# scHnRk_4.net
KiCad netlist of a schematic drawn in EAGLE
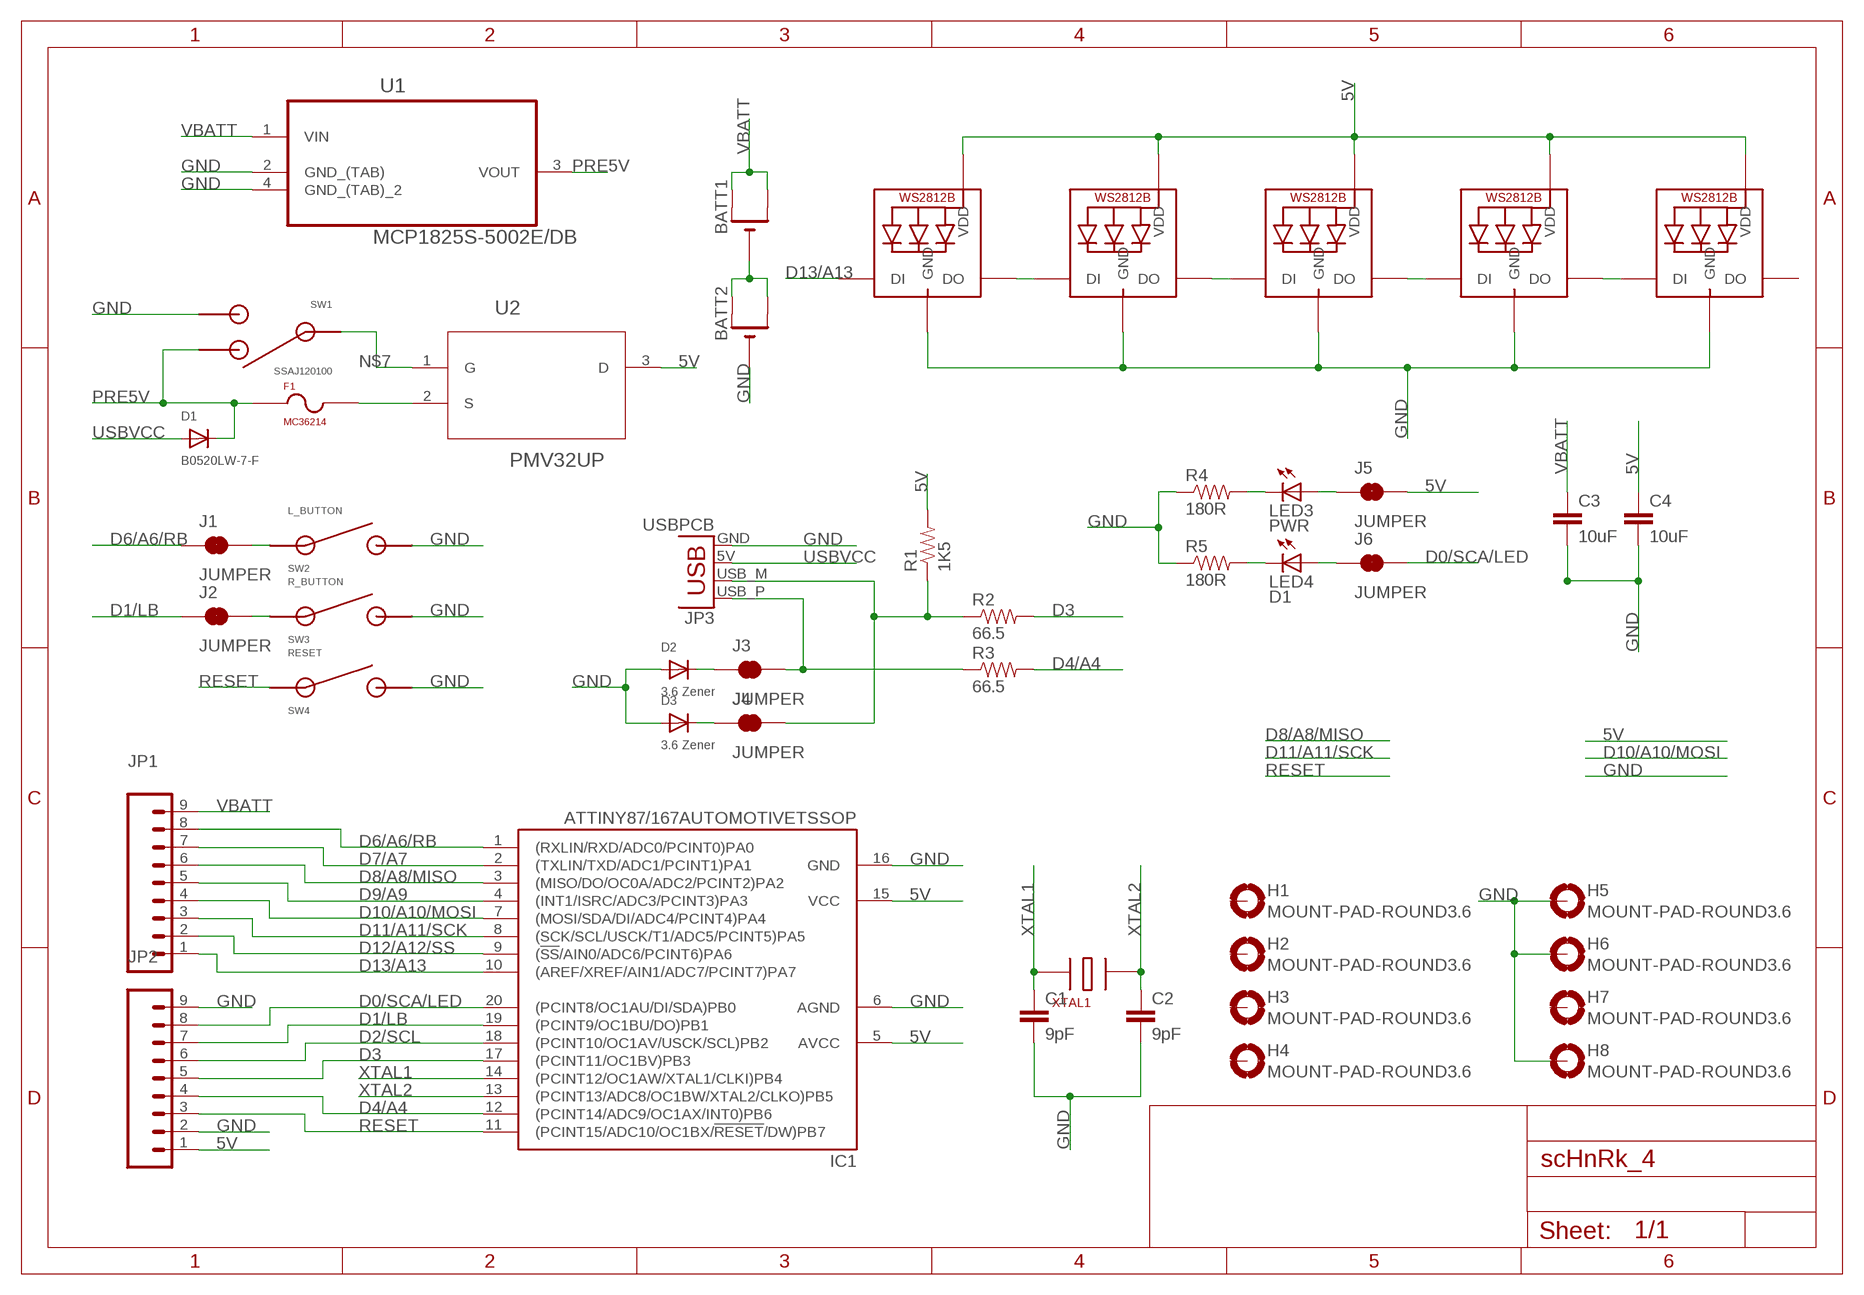
[diagram p0: schematic, sheet 1]

(export (version "E")
  (design (tool "Eeschema 10.0.6"))
  (components
    (comp (ref "BATT1")
      (value "CR2032SMT")
      (footprint "eagle-import:CR2032-SMD")
      (libsource (lib "eagle-import") (part "CR2032SMT"))
    )
    (comp (ref "BATT2")
      (value "CR2032SMT")
      (footprint "eagle-import:CR2032-SMD")
      (libsource (lib "eagle-import") (part "CR2032SMT"))
    )
    (comp (ref "C1")
      (value "9pF")
      (footprint "eagle-import:0603-CAP")
      (libsource (lib "eagle-import") (part "CAP0603-CAP"))
    )
    (comp (ref "C2")
      (value "9pF")
      (footprint "eagle-import:0603-CAP")
      (libsource (lib "eagle-import") (part "CAP0603-CAP"))
    )
    (comp (ref "C3")
      (value "10uF")
      (footprint "eagle-import:0805")
      (libsource (lib "eagle-import") (part "CAP0805"))
    )
    (comp (ref "C4")
      (value "10uF")
      (footprint "eagle-import:0805")
      (libsource (lib "eagle-import") (part "CAP0805"))
    )
    (comp (ref "D1")
      (value "B0520LW-7-F")
      (footprint "eagle-import:SOD-123")
      (libsource (lib "eagle-import") (part "DIODESOD-123"))
    )
    (comp (ref "D2")
      (value "3.6 Zener")
      (footprint "eagle-import:SOD-523")
      (libsource (lib "eagle-import") (part "DIODESOD-523"))
    )
    (comp (ref "D3")
      (value "3.6 Zener")
      (footprint "eagle-import:SOD-523")
      (libsource (lib "eagle-import") (part "DIODESOD-523"))
    )
    (comp (ref "F1")
      (value "MC36214")
      (footprint "eagle-import:MC36214")
      (libsource (lib "eagle-import") (part "MC36214"))
    )
    (comp (ref "H1")
      (value "MOUNT-PAD-ROUND3.6")
      (footprint "eagle-import:3,6-PAD")
      (libsource (lib "eagle-import") (part "MOUNT-PAD-ROUND3.6"))
    )
    (comp (ref "H2")
      (value "MOUNT-PAD-ROUND3.6")
      (footprint "eagle-import:3,6-PAD")
      (libsource (lib "eagle-import") (part "MOUNT-PAD-ROUND3.6"))
    )
    (comp (ref "H3")
      (value "MOUNT-PAD-ROUND3.6")
      (footprint "eagle-import:3,6-PAD")
      (libsource (lib "eagle-import") (part "MOUNT-PAD-ROUND3.6"))
    )
    (comp (ref "H4")
      (value "MOUNT-PAD-ROUND3.6")
      (footprint "eagle-import:3,6-PAD")
      (libsource (lib "eagle-import") (part "MOUNT-PAD-ROUND3.6"))
    )
    (comp (ref "H5")
      (value "MOUNT-PAD-ROUND3.6")
      (footprint "eagle-import:3,6-PAD")
      (libsource (lib "eagle-import") (part "MOUNT-PAD-ROUND3.6"))
    )
    (comp (ref "H6")
      (value "MOUNT-PAD-ROUND3.6")
      (footprint "eagle-import:3,6-PAD")
      (libsource (lib "eagle-import") (part "MOUNT-PAD-ROUND3.6"))
    )
    (comp (ref "H7")
      (value "MOUNT-PAD-ROUND3.6")
      (footprint "eagle-import:3,6-PAD")
      (libsource (lib "eagle-import") (part "MOUNT-PAD-ROUND3.6"))
    )
    (comp (ref "H8")
      (value "MOUNT-PAD-ROUND3.6")
      (footprint "eagle-import:3,6-PAD")
      (libsource (lib "eagle-import") (part "MOUNT-PAD-ROUND3.6"))
    )
    (comp (ref "IC1")
      (value "ATTINY87/167AUTOMOTIVETSSOP")
      (footprint "eagle-import:TSSOP20")
      (libsource (lib "eagle-import") (part "ATTINY87/167AUTOMOTIVETSSOP"))
    )
    (comp (ref "J1")
      (value "JUMPER")
      (footprint "eagle-import:PAD-JUMPER-2-NC_BY_TRACE_YES_SILK")
      (libsource (lib "eagle-import") (part "JUMPER-PAD-2-NC_BY_TRACE"))
    )
    (comp (ref "J2")
      (value "JUMPER")
      (footprint "eagle-import:PAD-JUMPER-2-NC_BY_TRACE_YES_SILK")
      (libsource (lib "eagle-import") (part "JUMPER-PAD-2-NC_BY_TRACE"))
    )
    (comp (ref "J3")
      (value "JUMPER")
      (footprint "eagle-import:PAD-JUMPER-2-NC_BY_TRACE_YES_SILK")
      (libsource (lib "eagle-import") (part "JUMPER-PAD-2-NC_BY_TRACE"))
    )
    (comp (ref "J4")
      (value "JUMPER")
      (footprint "eagle-import:PAD-JUMPER-2-NC_BY_TRACE_YES_SILK")
      (libsource (lib "eagle-import") (part "JUMPER-PAD-2-NC_BY_TRACE"))
    )
    (comp (ref "J5")
      (value "JUMPER")
      (footprint "eagle-import:PAD-JUMPER-2-NC_BY_TRACE_YES_SILK")
      (libsource (lib "eagle-import") (part "JUMPER-PAD-2-NC_BY_TRACE"))
    )
    (comp (ref "J6")
      (value "JUMPER")
      (footprint "eagle-import:PAD-JUMPER-2-NC_BY_TRACE_YES_SILK")
      (libsource (lib "eagle-import") (part "JUMPER-PAD-2-NC_BY_TRACE"))
    )
    (comp (ref "JP1")
      (value "M09")
      (footprint "eagle-import:1X09")
      (libsource (lib "eagle-import") (part "M09"))
    )
    (comp (ref "JP2")
      (value "M09")
      (footprint "eagle-import:1X09")
      (libsource (lib "eagle-import") (part "M09"))
    )
    (comp (ref "JP3")
      (value "USBPCB")
      (footprint "eagle-import:USB-A-PCB")
      (libsource (lib "eagle-import") (part "USBPCB"))
    )
    (comp (ref "LED1")
      (value "WS2812B5050")
      (footprint "eagle-import:WS2812B")
      (libsource (lib "eagle-import") (part "WS2812B5050"))
    )
    (comp (ref "LED2")
      (value "WS2812B5050")
      (footprint "eagle-import:WS2812B")
      (libsource (lib "eagle-import") (part "WS2812B5050"))
    )
    (comp (ref "LED3")
      (value "PWR")
      (footprint "eagle-import:CHIPLED_0603")
      (libsource (lib "eagle-import") (part "LEDCHIPLED_0603"))
    )
    (comp (ref "LED4")
      (value "D1")
      (footprint "eagle-import:CHIPLED_0603")
      (libsource (lib "eagle-import") (part "LEDCHIPLED_0603"))
    )
    (comp (ref "LED5")
      (value "WS2812B5050")
      (footprint "eagle-import:WS2812B")
      (libsource (lib "eagle-import") (part "WS2812B5050"))
    )
    (comp (ref "LED6")
      (value "WS2812B5050")
      (footprint "eagle-import:WS2812B")
      (libsource (lib "eagle-import") (part "WS2812B5050"))
    )
    (comp (ref "LED7")
      (value "WS2812B5050")
      (footprint "eagle-import:WS2812B")
      (libsource (lib "eagle-import") (part "WS2812B5050"))
    )
    (comp (ref "R1")
      (value "1K5")
      (footprint "eagle-import:0805")
      (libsource (lib "eagle-import") (part "RESISTOR0805-RES"))
    )
    (comp (ref "R2")
      (value "66.5")
      (footprint "eagle-import:0603-RES")
      (libsource (lib "eagle-import") (part "RESISTOR0603-RES"))
    )
    (comp (ref "R3")
      (value "66.5")
      (footprint "eagle-import:0603-RES")
      (libsource (lib "eagle-import") (part "RESISTOR0603-RES"))
    )
    (comp (ref "R4")
      (value "180R")
      (footprint "eagle-import:0805")
      (libsource (lib "eagle-import") (part "RESISTOR0805-RES"))
    )
    (comp (ref "R5")
      (value "180R")
      (footprint "eagle-import:0805")
      (libsource (lib "eagle-import") (part "RESISTOR0805-RES"))
    )
    (comp (ref "SW1")
      (value "SSAJ120100")
      (footprint "eagle-import:SSAJ120100")
      (libsource (lib "eagle-import") (part "SSAJ120100"))
    )
    (comp (ref "SW2")
      (value "L_BUTTON")
      (footprint "eagle-import:SKRBAGE010")
      (libsource (lib "eagle-import") (part "SKRBAGE010"))
    )
    (comp (ref "SW3")
      (value "R_BUTTON")
      (footprint "eagle-import:SKRBAGE010")
      (libsource (lib "eagle-import") (part "SKRBAGE010"))
    )
    (comp (ref "SW4")
      (value "RESET")
      (footprint "eagle-import:SKRBAGE010")
      (libsource (lib "eagle-import") (part "SKRBAGE010"))
    )
    (comp (ref "U1")
      (value "MCP1825S-5002E/DB")
      (footprint "eagle-import:SOT230P700X180-4N")
      (libsource (lib "eagle-import") (part "MCP1825S-5002E/DB"))
    )
    (comp (ref "U2")
      (value "PMV32UP")
      (footprint "eagle-import:SOT95P230X110-3N")
      (libsource (lib "eagle-import") (part "PMV32UP"))
    )
    (comp (ref "XTAL1")
      (value "16MHZ-2467444")
      (footprint "eagle-import:16MHZ-2467444")
      (libsource (lib "eagle-import") (part "16MHZ-2467444"))
    )
  )
  (nets
    (net (code "1") (name "/5V") (class "Default")
      (node (ref "C4") (pin "1") (pinfunction "1_1") (pintype "passive"))
      (node (ref "IC1") (pin "15") (pinfunction "VCC_15") (pintype "power_in"))
      (node (ref "IC1") (pin "5") (pinfunction "AVCC_5") (pintype "bidirectional"))
      (node (ref "J5") (pin "2") (pinfunction "2_2") (pintype "passive"))
      (node (ref "JP2") (pin "1") (pinfunction "1_1") (pintype "passive"))
      (node (ref "LED1") (pin "1-VDD") (pinfunction "VDD_1-VDD") (pintype "power_in"))
      (node (ref "LED2") (pin "1-VDD") (pinfunction "VDD_1-VDD") (pintype "power_in"))
      (node (ref "LED5") (pin "1-VDD") (pinfunction "VDD_1-VDD") (pintype "power_in"))
      (node (ref "LED6") (pin "1-VDD") (pinfunction "VDD_1-VDD") (pintype "power_in"))
      (node (ref "LED7") (pin "1-VDD") (pinfunction "VDD_1-VDD") (pintype "power_in"))
      (node (ref "R1") (pin "2") (pinfunction "2_2") (pintype "passive"))
      (node (ref "U2") (pin "3") (pinfunction "D_3") (pintype "passive"))
    )
    (net (code "2") (name "/D0{slash}SCA{slash}LED") (class "Default")
      (node (ref "IC1") (pin "20") (pinfunction "(PCINT8/OC1AU/DI/SDA)PB0_20") (pintype "bidirectional"))
      (node (ref "J6") (pin "2") (pinfunction "2_2") (pintype "passive"))
      (node (ref "JP2") (pin "8") (pinfunction "8_8") (pintype "passive"))
    )
    (net (code "3") (name "/D1{slash}LB") (class "Default")
      (node (ref "IC1") (pin "19") (pinfunction "(PCINT9/OC1BU/DO)PB1_19") (pintype "bidirectional"))
      (node (ref "J2") (pin "1") (pinfunction "1_1") (pintype "passive"))
      (node (ref "JP2") (pin "7") (pinfunction "7_7") (pintype "passive"))
    )
    (net (code "4") (name "/D2{slash}SCL") (class "Default")
      (node (ref "IC1") (pin "18") (pinfunction "(PCINT10/OC1AV/USCK/SCL)PB2_18") (pintype "bidirectional"))
      (node (ref "JP2") (pin "6") (pinfunction "6_6") (pintype "passive"))
    )
    (net (code "5") (name "/D3") (class "Default")
      (node (ref "IC1") (pin "17") (pinfunction "(PCINT11/OC1BV)PB3_17") (pintype "bidirectional"))
      (node (ref "JP2") (pin "5") (pinfunction "5_5") (pintype "passive"))
      (node (ref "R2") (pin "2") (pinfunction "2_2") (pintype "passive"))
    )
    (net (code "6") (name "/D4{slash}A4") (class "Default")
      (node (ref "IC1") (pin "12") (pinfunction "(PCINT14/ADC9/OC1AX/INT0)PB6_12") (pintype "bidirectional"))
      (node (ref "JP2") (pin "4") (pinfunction "4_4") (pintype "passive"))
      (node (ref "R3") (pin "2") (pinfunction "2_2") (pintype "passive"))
    )
    (net (code "7") (name "/D6{slash}A6{slash}RB") (class "Default")
      (node (ref "IC1") (pin "1") (pinfunction "(RXLIN/RXD/ADC0/PCINT0)PA0_1") (pintype "bidirectional"))
      (node (ref "J1") (pin "1") (pinfunction "1_1") (pintype "passive"))
      (node (ref "JP1") (pin "8") (pinfunction "8_8") (pintype "passive"))
    )
    (net (code "8") (name "/D7{slash}A7") (class "Default")
      (node (ref "IC1") (pin "2") (pinfunction "(TXLIN/TXD/ADC1/PCINT1)PA1_2") (pintype "bidirectional"))
      (node (ref "JP1") (pin "7") (pinfunction "7_7") (pintype "passive"))
    )
    (net (code "9") (name "/D8{slash}A8{slash}MISO") (class "Default")
      (node (ref "IC1") (pin "3") (pinfunction "(MISO/DO/OC0A/ADC2/PCINT2)PA2_3") (pintype "bidirectional"))
      (node (ref "JP1") (pin "6") (pinfunction "6_6") (pintype "passive"))
    )
    (net (code "10") (name "/D9{slash}A9") (class "Default")
      (node (ref "IC1") (pin "4") (pinfunction "(INT1/ISRC/ADC3/PCINT3)PA3_4") (pintype "bidirectional"))
      (node (ref "JP1") (pin "5") (pinfunction "5_5") (pintype "passive"))
    )
    (net (code "11") (name "/D10{slash}A10{slash}MOSI") (class "Default")
      (node (ref "IC1") (pin "7") (pinfunction "(MOSI/SDA/DI/ADC4/PCINT4)PA4_7") (pintype "bidirectional"))
      (node (ref "JP1") (pin "4") (pinfunction "4_4") (pintype "passive"))
    )
    (net (code "12") (name "/D11{slash}A11{slash}SCK") (class "Default")
      (node (ref "IC1") (pin "8") (pinfunction "(SCK/SCL/USCK/T1/ADC5/PCINT5)PA5_8") (pintype "bidirectional"))
      (node (ref "JP1") (pin "3") (pinfunction "3_3") (pintype "passive"))
    )
    (net (code "13") (name "/D12{slash}A12{slash}SS") (class "Default")
      (node (ref "IC1") (pin "9") (pinfunction "(~{SS}/AIN0/ADC6/PCINT6)PA6_9") (pintype "bidirectional"))
      (node (ref "JP1") (pin "2") (pinfunction "2_2") (pintype "passive"))
    )
    (net (code "14") (name "/D13{slash}A13") (class "Default")
      (node (ref "IC1") (pin "10") (pinfunction "(AREF/XREF/AIN1/ADC7/PCINT7)PA7_10") (pintype "bidirectional"))
      (node (ref "JP1") (pin "1") (pinfunction "1_1") (pintype "passive"))
      (node (ref "LED1") (pin "4-DIN") (pinfunction "DI_4-DIN") (pintype "input"))
    )
    (net (code "15") (name "/GND") (class "Default")
      (node (ref "BATT2") (pin "-") (pinfunction "-_-") (pintype "passive"))
      (node (ref "C1") (pin "2") (pinfunction "2_2") (pintype "passive"))
      (node (ref "C2") (pin "2") (pinfunction "2_2") (pintype "passive"))
      (node (ref "C3") (pin "2") (pinfunction "2_2") (pintype "passive"))
      (node (ref "C4") (pin "2") (pinfunction "2_2") (pintype "passive"))
      (node (ref "D2") (pin "A") (pinfunction "A_A") (pintype "passive"))
      (node (ref "D3") (pin "A") (pinfunction "A_A") (pintype "passive"))
      (node (ref "H5") (pin "B3,6") (pinfunction "MOUNT_B3,6") (pintype "passive"))
      (node (ref "H6") (pin "B3,6") (pinfunction "MOUNT_B3,6") (pintype "passive"))
      (node (ref "H8") (pin "B3,6") (pinfunction "MOUNT_B3,6") (pintype "passive"))
      (node (ref "IC1") (pin "16") (pinfunction "GND_16") (pintype "power_in"))
      (node (ref "IC1") (pin "6") (pinfunction "AGND_6") (pintype "bidirectional"))
      (node (ref "JP2") (pin "2") (pinfunction "2_2") (pintype "passive"))
      (node (ref "JP2") (pin "9") (pinfunction "9_9") (pintype "passive"))
      (node (ref "JP3") (pin "GND") (pinfunction "GND_GND") (pintype "bidirectional"))
      (node (ref "LED1") (pin "3-GND") (pinfunction "GND_3-GND") (pintype "power_in"))
      (node (ref "LED2") (pin "3-GND") (pinfunction "GND_3-GND") (pintype "power_in"))
      (node (ref "LED5") (pin "3-GND") (pinfunction "GND_3-GND") (pintype "power_in"))
      (node (ref "LED6") (pin "3-GND") (pinfunction "GND_3-GND") (pintype "power_in"))
      (node (ref "LED7") (pin "3-GND") (pinfunction "GND_3-GND") (pintype "power_in"))
      (node (ref "R4") (pin "1") (pinfunction "1_1") (pintype "passive"))
      (node (ref "R5") (pin "1") (pinfunction "1_1") (pintype "passive"))
      (node (ref "SW1") (pin "P$2") (pinfunction "P$2_P$2") (pintype "bidirectional"))
      (node (ref "SW2") (pin "P$2") (pinfunction "P$2_P$2") (pintype "bidirectional"))
      (node (ref "SW2") (pin "P$4") (pinfunction "P$2_P$4") (pintype "bidirectional"))
      (node (ref "SW3") (pin "P$2") (pinfunction "P$2_P$2") (pintype "bidirectional"))
      (node (ref "SW3") (pin "P$4") (pinfunction "P$2_P$4") (pintype "bidirectional"))
      (node (ref "SW4") (pin "P$2") (pinfunction "P$2_P$2") (pintype "bidirectional"))
      (node (ref "SW4") (pin "P$4") (pinfunction "P$2_P$4") (pintype "bidirectional"))
      (node (ref "U1") (pin "2") (pinfunction "GND_(TAB)_2") (pintype "passive"))
      (node (ref "U1") (pin "4") (pinfunction "GND_(TAB)_2_4") (pintype "passive"))
    )
    (net (code "16") (name "/N$7") (class "Default")
      (node (ref "SW1") (pin "P$C") (pinfunction "P$C_P$C") (pintype "bidirectional"))
      (node (ref "U2") (pin "1") (pinfunction "G_1") (pintype "passive"))
    )
    (net (code "17") (name "/PRE5V") (class "Default")
      (node (ref "D1") (pin "C") (pinfunction "C_C") (pintype "passive"))
      (node (ref "F1") (pin "P$1") (pinfunction "P$1_P$1") (pintype "bidirectional"))
      (node (ref "SW1") (pin "P$1") (pinfunction "P$1_P$1") (pintype "bidirectional"))
      (node (ref "U1") (pin "3") (pinfunction "VOUT_3") (pintype "output"))
    )
    (net (code "18") (name "/RESET") (class "Default")
      (node (ref "IC1") (pin "11") (pinfunction "(PCINT15/ADC10/OC1BX/~{RESET}/DW)PB7_11") (pintype "bidirectional"))
      (node (ref "JP2") (pin "3") (pinfunction "3_3") (pintype "passive"))
      (node (ref "SW4") (pin "P$1") (pinfunction "P$1_P$1") (pintype "bidirectional"))
      (node (ref "SW4") (pin "P$3") (pinfunction "P$1_P$3") (pintype "bidirectional"))
    )
    (net (code "19") (name "/USBVCC") (class "Default")
      (node (ref "D1") (pin "A") (pinfunction "A_A") (pintype "passive"))
      (node (ref "JP3") (pin "5V") (pinfunction "VBUS_5V") (pintype "bidirectional"))
    )
    (net (code "20") (name "/VBATT") (class "Default")
      (node (ref "BATT1") (pin "+$1") (pinfunction "+_+$1") (pintype "passive"))
      (node (ref "BATT1") (pin "+$2") (pinfunction "+1_+$2") (pintype "passive"))
      (node (ref "C3") (pin "1") (pinfunction "1_1") (pintype "passive"))
      (node (ref "JP1") (pin "9") (pinfunction "9_9") (pintype "passive"))
      (node (ref "U1") (pin "1") (pinfunction "VIN_1") (pintype "input"))
    )
    (net (code "21") (name "/XTAL1") (class "Default")
      (node (ref "C1") (pin "1") (pinfunction "1_1") (pintype "passive"))
      (node (ref "IC1") (pin "14") (pinfunction "(PCINT12/OC1AW/XTAL1/CLKI)PB4_14") (pintype "bidirectional"))
      (node (ref "XTAL1") (pin "P$1") (pinfunction "P$1_P$1") (pintype "bidirectional"))
    )
    (net (code "22") (name "/XTAL2") (class "Default")
      (node (ref "C2") (pin "1") (pinfunction "1_1") (pintype "passive"))
      (node (ref "IC1") (pin "13") (pinfunction "(PCINT13/ADC8/OC1BW/XTAL2/CLKO)PB5_13") (pintype "bidirectional"))
      (node (ref "XTAL1") (pin "P$3") (pinfunction "P$2_P$3") (pintype "bidirectional"))
    )
    (net (code "23") (name "Net-(BATT2-+)") (class "Default")
      (node (ref "BATT1") (pin "-") (pinfunction "-_-") (pintype "passive"))
      (node (ref "BATT2") (pin "+$1") (pinfunction "+_+$1") (pintype "passive"))
      (node (ref "BATT2") (pin "+$2") (pinfunction "+1_+$2") (pintype "passive"))
    )
    (net (code "24") (name "Net-(D2-C)") (class "Default")
      (node (ref "D2") (pin "K") (pinfunction "C_K") (pintype "passive"))
      (node (ref "J3") (pin "1") (pinfunction "1_1") (pintype "passive"))
    )
    (net (code "25") (name "Net-(D3-C)") (class "Default")
      (node (ref "D3") (pin "K") (pinfunction "C_K") (pintype "passive"))
      (node (ref "J4") (pin "1") (pinfunction "1_1") (pintype "passive"))
    )
    (net (code "26") (name "Net-(J1-Pad2)") (class "Default")
      (node (ref "J1") (pin "2") (pinfunction "2_2") (pintype "passive"))
      (node (ref "SW2") (pin "P$1") (pinfunction "P$1_P$1") (pintype "bidirectional"))
      (node (ref "SW2") (pin "P$3") (pinfunction "P$1_P$3") (pintype "bidirectional"))
    )
    (net (code "27") (name "Net-(J2-Pad2)") (class "Default")
      (node (ref "J2") (pin "2") (pinfunction "2_2") (pintype "passive"))
      (node (ref "SW3") (pin "P$1") (pinfunction "P$1_P$1") (pintype "bidirectional"))
      (node (ref "SW3") (pin "P$3") (pinfunction "P$1_P$3") (pintype "bidirectional"))
    )
    (net (code "28") (name "Net-(J5-Pad1)") (class "Default")
      (node (ref "J5") (pin "1") (pinfunction "1_1") (pintype "passive"))
      (node (ref "LED3") (pin "A") (pinfunction "A_A") (pintype "passive"))
    )
    (net (code "29") (name "Net-(J6-Pad1)") (class "Default")
      (node (ref "J6") (pin "1") (pinfunction "1_1") (pintype "passive"))
      (node (ref "LED4") (pin "A") (pinfunction "A_A") (pintype "passive"))
    )
    (net (code "30") (name "Net-(JP3-D+)") (class "Default")
      (node (ref "J3") (pin "2") (pinfunction "2_2") (pintype "passive"))
      (node (ref "JP3") (pin "USB_P") (pinfunction "D+_USB_P") (pintype "bidirectional"))
      (node (ref "R3") (pin "1") (pinfunction "1_1") (pintype "passive"))
    )
    (net (code "31") (name "Net-(JP3-D-)") (class "Default")
      (node (ref "J4") (pin "2") (pinfunction "2_2") (pintype "passive"))
      (node (ref "JP3") (pin "USB_M") (pinfunction "D-_USB_M") (pintype "bidirectional"))
      (node (ref "R1") (pin "1") (pinfunction "1_1") (pintype "passive"))
      (node (ref "R2") (pin "1") (pinfunction "1_1") (pintype "passive"))
    )
    (net (code "32") (name "Net-(LED1-DO)") (class "Default")
      (node (ref "LED1") (pin "2-DOUT") (pinfunction "DO_2-DOUT") (pintype "output"))
      (node (ref "LED2") (pin "4-DIN") (pinfunction "DI_4-DIN") (pintype "input"))
    )
    (net (code "33") (name "Net-(LED2-DO)") (class "Default")
      (node (ref "LED2") (pin "2-DOUT") (pinfunction "DO_2-DOUT") (pintype "output"))
      (node (ref "LED5") (pin "4-DIN") (pinfunction "DI_4-DIN") (pintype "input"))
    )
    (net (code "34") (name "Net-(LED3-PadC)") (class "Default")
      (node (ref "LED3") (pin "C") (pinfunction "C_C") (pintype "passive"))
      (node (ref "R4") (pin "2") (pinfunction "2_2") (pintype "passive"))
    )
    (net (code "35") (name "Net-(LED4-PadC)") (class "Default")
      (node (ref "LED4") (pin "C") (pinfunction "C_C") (pintype "passive"))
      (node (ref "R5") (pin "2") (pinfunction "2_2") (pintype "passive"))
    )
    (net (code "36") (name "Net-(LED5-DO)") (class "Default")
      (node (ref "LED5") (pin "2-DOUT") (pinfunction "DO_2-DOUT") (pintype "output"))
      (node (ref "LED6") (pin "4-DIN") (pinfunction "DI_4-DIN") (pintype "input"))
    )
    (net (code "37") (name "Net-(LED6-DO)") (class "Default")
      (node (ref "LED6") (pin "2-DOUT") (pinfunction "DO_2-DOUT") (pintype "output"))
      (node (ref "LED7") (pin "4-DIN") (pinfunction "DI_4-DIN") (pintype "input"))
    )
    (net (code "38") (name "Net-(U2-S)") (class "Default")
      (node (ref "F1") (pin "P$2") (pinfunction "P$2_P$2") (pintype "bidirectional"))
      (node (ref "U2") (pin "2") (pinfunction "S_2") (pintype "passive"))
    )
    (net (code "39") (name "unconnected-(H1-MOUNT-PadB3,6)") (class "Default")
      (node (ref "H1") (pin "B3,6") (pinfunction "MOUNT_B3,6") (pintype "passive"))
    )
    (net (code "40") (name "unconnected-(H2-MOUNT-PadB3,6)") (class "Default")
      (node (ref "H2") (pin "B3,6") (pinfunction "MOUNT_B3,6") (pintype "passive"))
    )
    (net (code "41") (name "unconnected-(H3-MOUNT-PadB3,6)") (class "Default")
      (node (ref "H3") (pin "B3,6") (pinfunction "MOUNT_B3,6") (pintype "passive"))
    )
    (net (code "42") (name "unconnected-(H4-MOUNT-PadB3,6)") (class "Default")
      (node (ref "H4") (pin "B3,6") (pinfunction "MOUNT_B3,6") (pintype "passive"))
    )
    (net (code "43") (name "unconnected-(H7-MOUNT-PadB3,6)") (class "Default")
      (node (ref "H7") (pin "B3,6") (pinfunction "MOUNT_B3,6") (pintype "passive"))
    )
    (net (code "44") (name "unconnected-(LED7-DO-Pad2-DOUT)") (class "Default")
      (node (ref "LED7") (pin "2-DOUT") (pinfunction "DO_2-DOUT") (pintype "output"))
    )
  )
)
